# power_dist.net
KiCad netlist of a schematic drawn in EAGLE
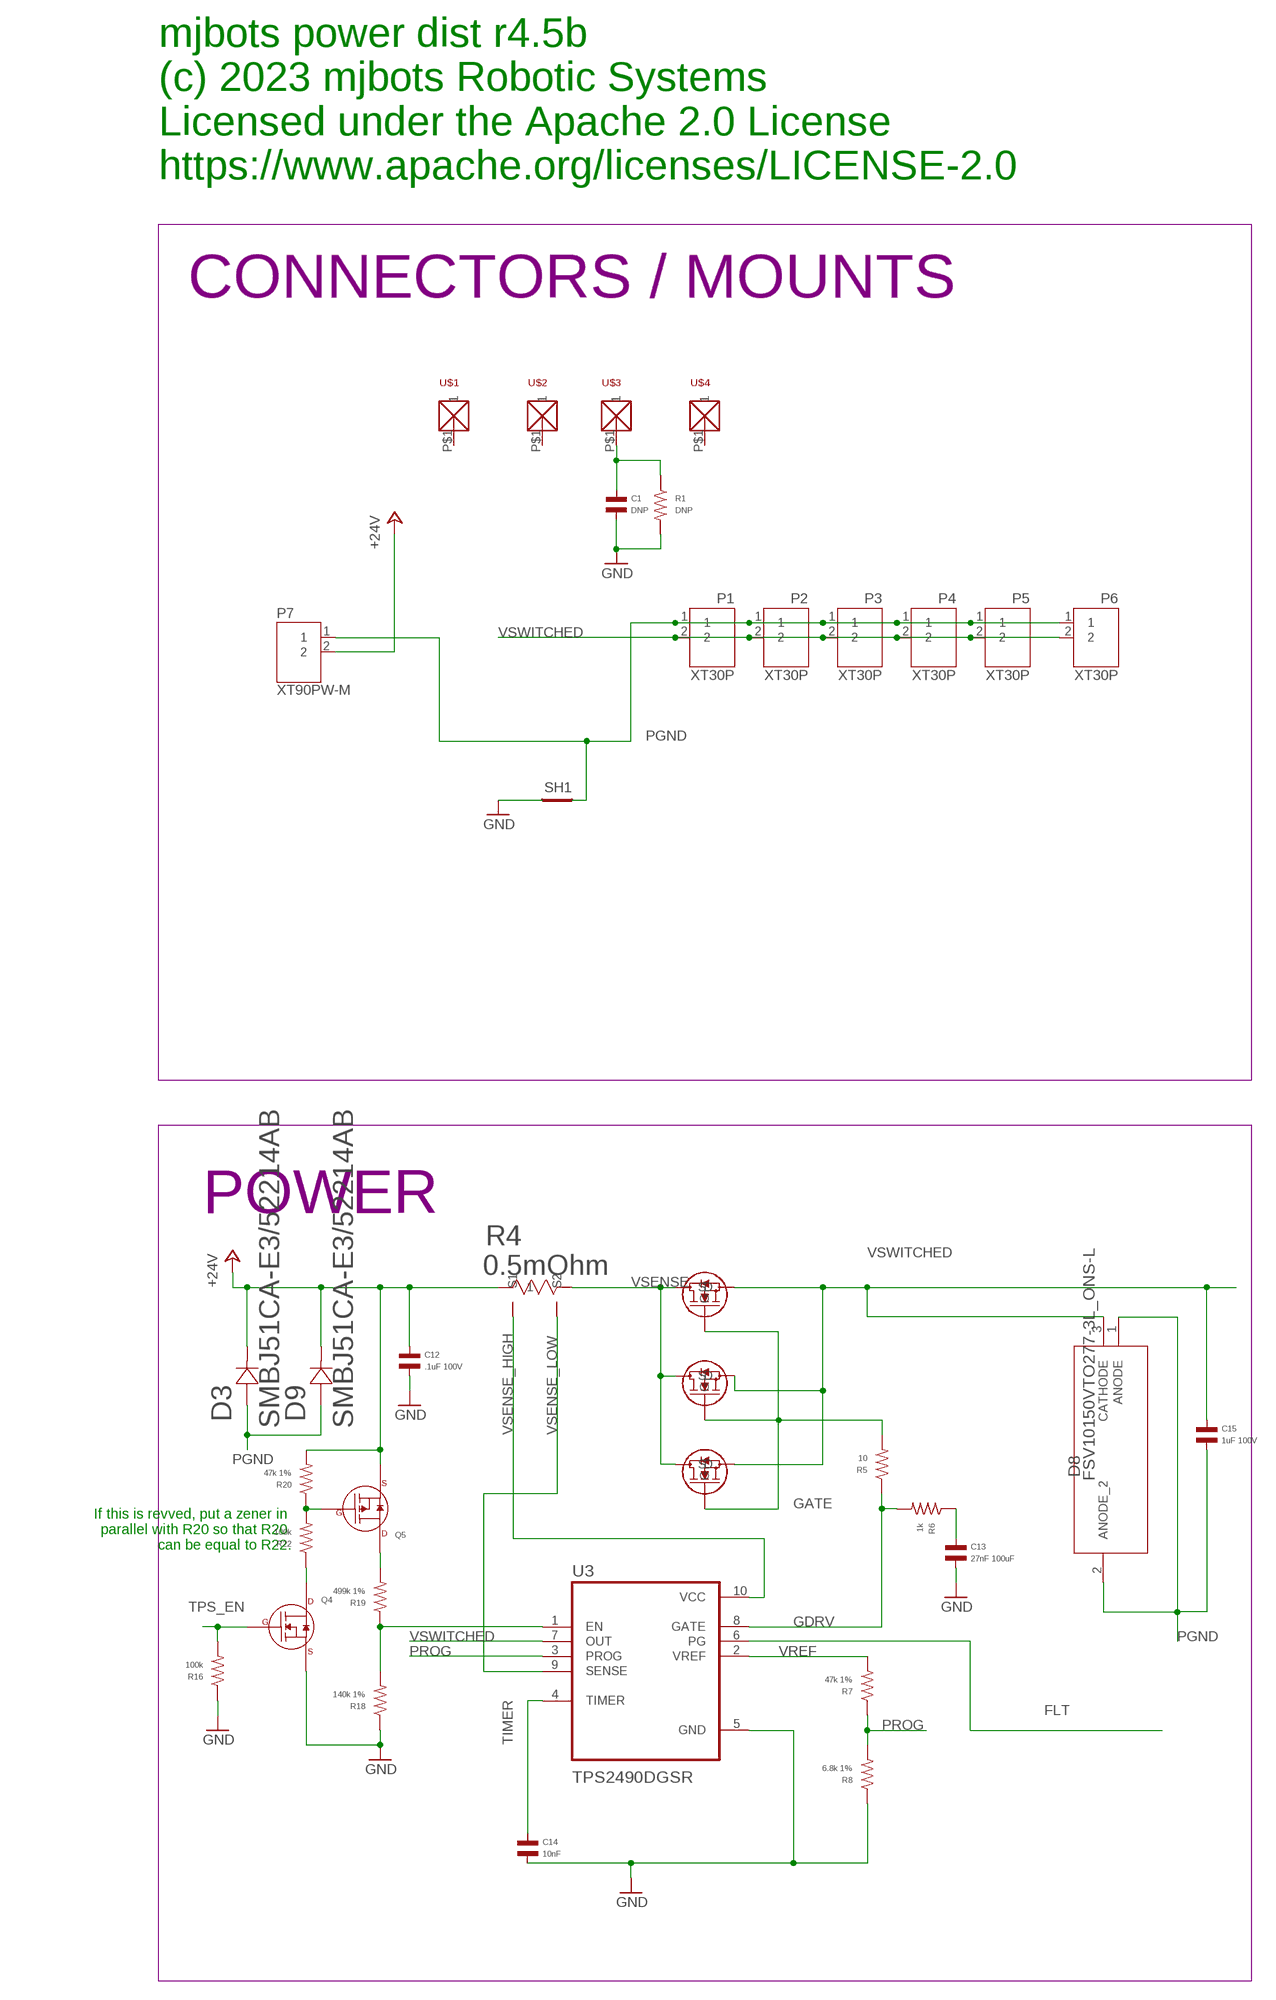
[diagram p0: schematic, sheet 1, part 1 of 2]
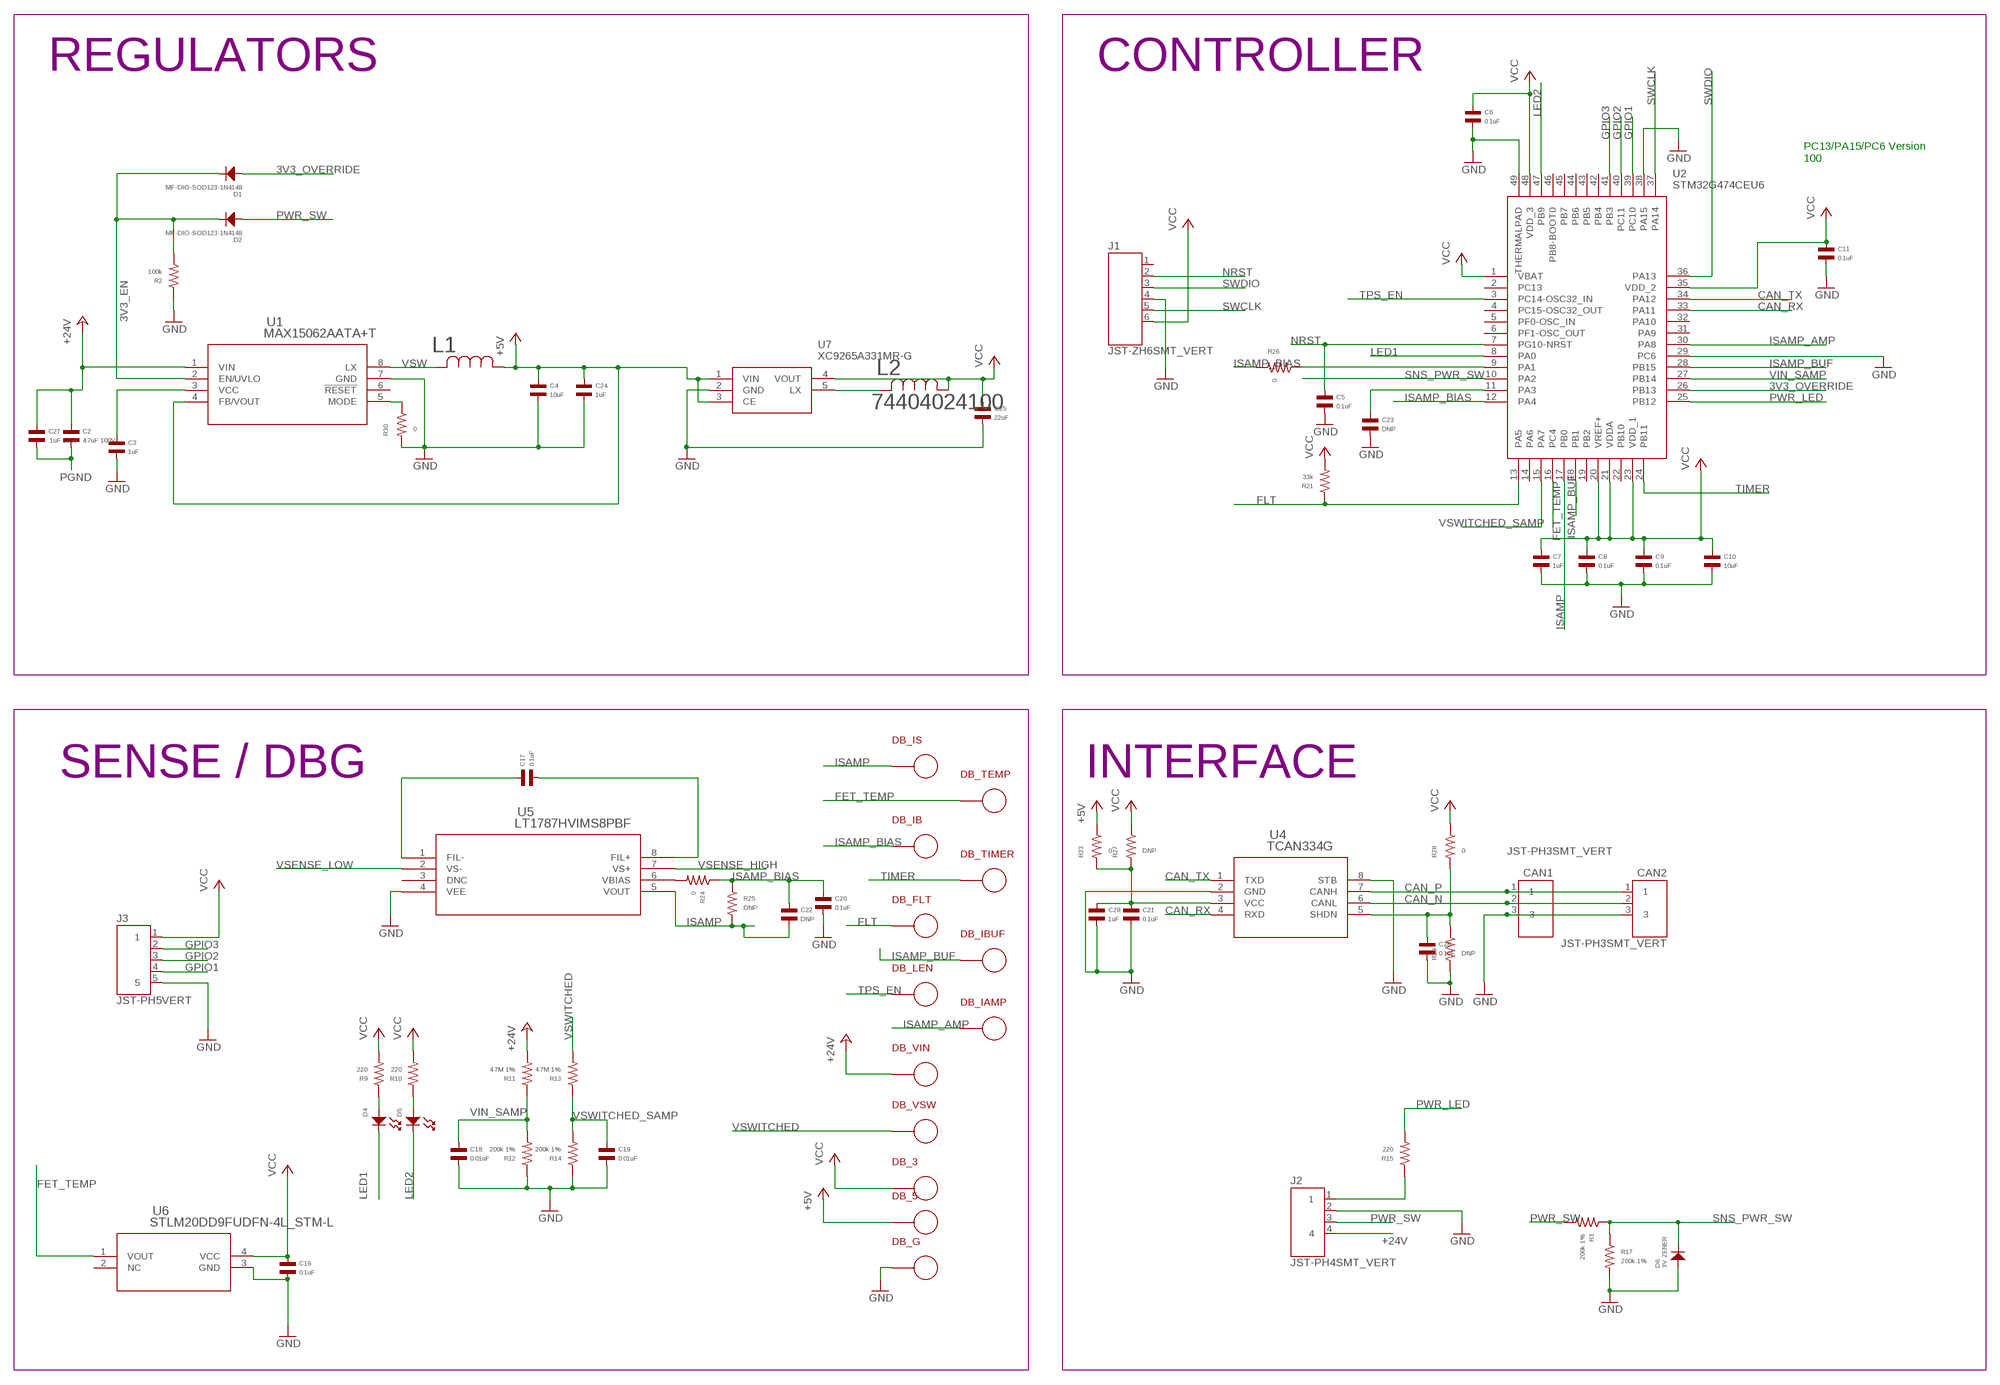
[diagram p1: schematic, sheet 1, part 2 of 2]

(export (version "E")
  (design (tool "Eeschema 10.0.6"))
  (components
    (comp (ref "C1")
      (value "DNP")
      (footprint "eagle-import:C0603")
      (fields (field (name "POPULATE") "0"))
      (libsource (lib "eagle-import") (part "CAPACITOR_NP_0603"))
    )
    (comp (ref "C2")
      (value "4.7uF 100V")
      (footprint "eagle-import:C1206")
      (fields (field (name "MF") "MURATA") (field (name "MPN") "GRJ31CC72A475KE01K"))
      (libsource (lib "eagle-import") (part "CAPACITOR_NP_1206"))
    )
    (comp (ref "C3")
      (value "1uF")
      (footprint "eagle-import:C0603")
      (fields (field (name "HOUSEPART") "1") (field (name "MPN") "MF-CAP-0603-1uF"))
      (libsource (lib "eagle-import") (part "CAPACITOR_NP_0603"))
    )
    (comp (ref "C4")
      (value "10uF")
      (footprint "eagle-import:C1206")
      (fields (field (name "HOUSEPART") "1") (field (name "MPN") "MF-CAP-1206-10uF"))
      (libsource (lib "eagle-import") (part "CAPACITOR_NP_1206"))
    )
    (comp (ref "C5")
      (value "0.1uF")
      (footprint "eagle-import:C0603")
      (fields (field (name "HOUSEPART") "1") (field (name "MPN") "MF-CAP-0603-0.1uF"))
      (libsource (lib "eagle-import") (part "CAPACITOR_NP_0603"))
    )
    (comp (ref "C6")
      (value "0.1uF")
      (footprint "eagle-import:C0603")
      (fields (field (name "HOUSEPART") "1") (field (name "MPN") "MF-CAP-0603-0.1uF"))
      (libsource (lib "eagle-import") (part "CAPACITOR_NP_0603"))
    )
    (comp (ref "C7")
      (value "1uF")
      (footprint "eagle-import:C0603")
      (fields (field (name "HOUSEPART") "1") (field (name "MPN") "MF-CAP-0603-1uF"))
      (libsource (lib "eagle-import") (part "CAPACITOR_NP_0603"))
    )
    (comp (ref "C8")
      (value "0.1uF")
      (footprint "eagle-import:C0603")
      (fields (field (name "HOUSEPART") "1") (field (name "MPN") "MF-CAP-0603-0.1uF"))
      (libsource (lib "eagle-import") (part "CAPACITOR_NP_0603"))
    )
    (comp (ref "C9")
      (value "0.1uF")
      (footprint "eagle-import:C0603")
      (fields (field (name "HOUSEPART") "1") (field (name "MPN") "MF-CAP-0603-0.1uF"))
      (libsource (lib "eagle-import") (part "CAPACITOR_NP_0603"))
    )
    (comp (ref "C10")
      (value "10uF")
      (footprint "eagle-import:C1206")
      (fields (field (name "HOUSEPART") "1") (field (name "MPN") "MF-CAP-1206-10uF"))
      (libsource (lib "eagle-import") (part "CAPACITOR_NP_1206"))
    )
    (comp (ref "C11")
      (value "0.1uF")
      (footprint "eagle-import:C0603")
      (fields (field (name "HOUSEPART") "1") (field (name "MPN") "MF-CAP-0603-0.1uF"))
      (libsource (lib "eagle-import") (part "CAPACITOR_NP_0603"))
    )
    (comp (ref "C12")
      (value ".1uF 100V")
      (footprint "eagle-import:C0603")
      (fields (field (name "HOUSEPART") "0") (field (name "MPN") "GRM188R72A104KA35D"))
      (libsource (lib "eagle-import") (part "CAPACITOR_NP_0603"))
    )
    (comp (ref "C13")
      (value "27nF 100uF")
      (footprint "eagle-import:C0603")
      (fields (field (name "HOUSEPART") "0") (field (name "MPN") "C0603C273K1RAC7867"))
      (libsource (lib "eagle-import") (part "CAPACITOR_NP_0603"))
    )
    (comp (ref "C14")
      (value "10nF")
      (footprint "eagle-import:C0603")
      (fields (field (name "HOUSEPART") "1") (field (name "MPN") "MF-CAP-0603-0.01uF"))
      (libsource (lib "eagle-import") (part "CAPACITOR_NP_0603"))
    )
    (comp (ref "C15")
      (value "1uF 100V")
      (footprint "eagle-import:C0805")
      (fields (field (name "MF") "MURATA") (field (name "MPN") "GCM21BC72A105KE36L"))
      (libsource (lib "eagle-import") (part "CAPACITOR_NP_0805"))
    )
    (comp (ref "C16")
      (value "0.1uF")
      (footprint "eagle-import:C0603")
      (fields (field (name "HOUSEPART") "1") (field (name "MPN") "MF-CAP-0603-0.1uF"))
      (libsource (lib "eagle-import") (part "CAPACITOR_NP_0603"))
    )
    (comp (ref "C17")
      (value "0.1uF")
      (footprint "eagle-import:C0603")
      (fields (field (name "HOUSEPART") "1") (field (name "MPN") "MF-CAP-0603-0.1uF"))
      (libsource (lib "eagle-import") (part "CAPACITOR_NP_0603"))
    )
    (comp (ref "C18")
      (value "0.01uF")
      (footprint "eagle-import:C0603")
      (fields (field (name "HOUSEPART") "1") (field (name "MPN") "MF-CAP-0603-0.01uF"))
      (libsource (lib "eagle-import") (part "CAPACITOR_NP_0603"))
    )
    (comp (ref "C19")
      (value "0.01uF")
      (footprint "eagle-import:C0603")
      (fields (field (name "HOUSEPART") "1") (field (name "MPN") "MF-CAP-0603-0.01uF"))
      (libsource (lib "eagle-import") (part "CAPACITOR_NP_0603"))
    )
    (comp (ref "C20")
      (value "0.1uF")
      (footprint "eagle-import:C0603")
      (fields (field (name "HOUSEPART") "1") (field (name "MPN") "MF-CAP-0603-0.1uF"))
      (libsource (lib "eagle-import") (part "CAPACITOR_NP_0603"))
    )
    (comp (ref "C21")
      (value "0.1uF")
      (footprint "eagle-import:C0603")
      (fields (field (name "HOUSEPART") "1") (field (name "MPN") "MF-CAP-0603-0.1uF"))
      (libsource (lib "eagle-import") (part "CAPACITOR_NP_0603"))
    )
    (comp (ref "C22")
      (value "DNP")
      (footprint "eagle-import:C0603")
      (fields (field (name "HOUSEPART") "1") (field (name "POPULATE") "0"))
      (libsource (lib "eagle-import") (part "CAPACITOR_NP_0603"))
    )
    (comp (ref "C23")
      (value "DNP")
      (footprint "eagle-import:C0603")
      (fields (field (name "HOUSEPART") "1") (field (name "POPULATE") "0"))
      (libsource (lib "eagle-import") (part "CAPACITOR_NP_0603"))
    )
    (comp (ref "C24")
      (value "1uF")
      (footprint "eagle-import:C0402")
      (fields (field (name "HOUSEPART") "1") (field (name "MPN") "MF-CAP-0402-1uF"))
      (libsource (lib "eagle-import") (part "CAPACITOR_NP_0402"))
    )
    (comp (ref "C25")
      (value "22uF")
      (footprint "eagle-import:C1206")
      (fields (field (name "MF") "Samsung") (field (name "MPN") "CL31B226KPHNNNE"))
      (libsource (lib "eagle-import") (part "CAPACITOR_NP_1206"))
    )
    (comp (ref "C26")
      (value "0.1uF")
      (footprint "eagle-import:C0603")
      (fields (field (name "HOUSEPART") "1") (field (name "MPN") "MF-CAP-0603-0.1uF"))
      (libsource (lib "eagle-import") (part "CAPACITOR_NP_0603"))
    )
    (comp (ref "C27")
      (value ".1uF 100V")
      (footprint "eagle-import:C0603")
      (fields (field (name "HOUSEPART") "0") (field (name "MPN") "GRM188R72A104KA35D"))
      (libsource (lib "eagle-import") (part "CAPACITOR_NP_0603"))
    )
    (comp (ref "C28")
      (value "1uF")
      (footprint "eagle-import:C0603")
      (fields (field (name "HOUSEPART") "1") (field (name "MPN") "MF-CAP-0603-1uF"))
      (libsource (lib "eagle-import") (part "CAPACITOR_NP_0603"))
    )
    (comp (ref "CAN1")
      (value "JST-PH3SMT_VERT")
      (footprint "eagle-import:JST_B3B_PH-SM4-TB(LF)(SN)")
      (fields (field (name "MF") "JST") (field (name "MPN") "B3B-PH-SM4-TB(LF)(SN)"))
      (libsource (lib "eagle-import") (part "JST-PH3SMT_VERT"))
    )
    (comp (ref "CAN2")
      (value "JST-PH3SMT_VERT")
      (footprint "eagle-import:JST_B3B_PH-SM4-TB(LF)(SN)")
      (fields (field (name "MF") "JST") (field (name "MPN") "B3B-PH-SM4-TB(LF)(SN)"))
      (libsource (lib "eagle-import") (part "JST-PH3SMT_VERT"))
    )
    (comp (ref "D1")
      (value "MF-DIO-SOD123-1N4148")
      (footprint "eagle-import:SOD-123")
      (fields (field (name "HOUSEPART") "YES"))
      (libsource (lib "eagle-import") (part "DIODES_SOD-123_1N4148"))
    )
    (comp (ref "D2")
      (value "MF-DIO-SOD123-1N4148")
      (footprint "eagle-import:SOD-123")
      (fields (field (name "HOUSEPART") "YES"))
      (libsource (lib "eagle-import") (part "DIODES_SOD-123_1N4148"))
    )
    (comp (ref "D3")
      (value "SMBJ51CA-E3/52214AB")
      (footprint "eagle-import:DIODE_DO-214AB")
      (fields (field (name "MPN") "SMC5K51A-M3/I"))
      (libsource (lib "eagle-import") (part "SMBJ51CA-E3/52214AB"))
    )
    (comp (ref "D4")
      (value "LED_SINGLE-0603")
      (footprint "eagle-import:LED0603")
      (fields
        (field (name "HOUSEPART") "NO")
        (field (name "HOUSEPART_1") "1")
        (field (name "MPN") "MF-LED-0603-RED")
      )
      (libsource (lib "eagle-import") (part "LED_SINGLE-0603"))
    )
    (comp (ref "D5")
      (value "LED_SINGLE-0603")
      (footprint "eagle-import:LED0603")
      (fields
        (field (name "HOUSEPART") "NO")
        (field (name "HOUSEPART_1") "1")
        (field (name "MPN") "MF-LED-0603-RED")
      )
      (libsource (lib "eagle-import") (part "LED_SINGLE-0603"))
    )
    (comp (ref "D6")
      (value "3V ZENER")
      (footprint "eagle-import:SOD-123")
      (fields
        (field (name "HOUSEPART") "YES")
        (field (name "MPN") "MF-DIO-SOD123-1N4148")
        (field (name "MPN_1") "MMSZ4682T1G")
      )
      (libsource (lib "eagle-import") (part "DIODES_SOD-123_1N4148"))
    )
    (comp (ref "D8")
      (value "FSV10150VTO277-3L_ONS-L")
      (footprint "eagle-import:TO277-3L_ONS-L")
      (fields
        (field (name "MANUFACTURER_PART_NUMBER") "FSV10150V")
        (field (name "COPYRIGHT") "Copyright (C) 2018 Accelerated Designs. All rights reserved")
      )
      (libsource (lib "eagle-import") (part "FSV10150VTO277-3L_ONS-L"))
    )
    (comp (ref "D9")
      (value "SMBJ51CA-E3/52214AB")
      (footprint "eagle-import:DIODE_DO-214AB")
      (fields (field (name "MPN") "SMC5K51A-M3/I"))
      (libsource (lib "eagle-import") (part "SMBJ51CA-E3/52214AB"))
    )
    (comp (ref "DB_3")
      (value "PAD24AWG_PAD")
      (footprint "eagle-import:24AWG_PAD")
      (libsource (lib "eagle-import") (part "PAD24AWG_PAD"))
    )
    (comp (ref "DB_5")
      (value "PAD24AWG_PAD")
      (footprint "eagle-import:24AWG_PAD")
      (libsource (lib "eagle-import") (part "PAD24AWG_PAD"))
    )
    (comp (ref "DB_FLT")
      (value "PAD24AWG_PAD")
      (footprint "eagle-import:24AWG_PAD")
      (libsource (lib "eagle-import") (part "PAD24AWG_PAD"))
    )
    (comp (ref "DB_G")
      (value "PAD24AWG_PAD")
      (footprint "eagle-import:24AWG_PAD")
      (libsource (lib "eagle-import") (part "PAD24AWG_PAD"))
    )
    (comp (ref "DB_IAMP")
      (value "PAD24AWG_PAD")
      (footprint "eagle-import:24AWG_PAD")
      (libsource (lib "eagle-import") (part "PAD24AWG_PAD"))
    )
    (comp (ref "DB_IB")
      (value "PAD24AWG_PAD")
      (footprint "eagle-import:24AWG_PAD")
      (libsource (lib "eagle-import") (part "PAD24AWG_PAD"))
    )
    (comp (ref "DB_IBUF")
      (value "PAD24AWG_PAD")
      (footprint "eagle-import:24AWG_PAD")
      (libsource (lib "eagle-import") (part "PAD24AWG_PAD"))
    )
    (comp (ref "DB_IS")
      (value "PAD24AWG_PAD")
      (footprint "eagle-import:24AWG_PAD")
      (libsource (lib "eagle-import") (part "PAD24AWG_PAD"))
    )
    (comp (ref "DB_LEN")
      (value "PAD24AWG_PAD")
      (footprint "eagle-import:24AWG_PAD")
      (libsource (lib "eagle-import") (part "PAD24AWG_PAD"))
    )
    (comp (ref "DB_TEMP")
      (value "PAD24AWG_PAD")
      (footprint "eagle-import:24AWG_PAD")
      (libsource (lib "eagle-import") (part "PAD24AWG_PAD"))
    )
    (comp (ref "DB_TIMER")
      (value "PAD24AWG_PAD")
      (footprint "eagle-import:24AWG_PAD")
      (libsource (lib "eagle-import") (part "PAD24AWG_PAD"))
    )
    (comp (ref "DB_VIN")
      (value "PAD24AWG_PAD")
      (footprint "eagle-import:24AWG_PAD")
      (libsource (lib "eagle-import") (part "PAD24AWG_PAD"))
    )
    (comp (ref "DB_VSW")
      (value "PAD24AWG_PAD")
      (footprint "eagle-import:24AWG_PAD")
      (libsource (lib "eagle-import") (part "PAD24AWG_PAD"))
    )
    (comp (ref "J1")
      (value "JST-ZH6SMT_VERT")
      (footprint "eagle-import:JST_B6B-ZR-SM4-TF(LF)(SN)")
      (fields (field (name "MF") "JST") (field (name "MPN") "B6B-ZR-SM4-TF(LF)(SN)"))
      (libsource (lib "eagle-import") (part "JST-ZH6SMT_VERT"))
    )
    (comp (ref "J2")
      (value "JST-PH4SMT_VERT")
      (footprint "eagle-import:JST_B4B_PH-SM4-TB(LF)(SN)")
      (fields (field (name "MF") "JST") (field (name "MPN") "B4B-PH-SM4-TB(LF)(SN)"))
      (libsource (lib "eagle-import") (part "JST-PH4SMT_VERT"))
    )
    (comp (ref "J3")
      (value "JST-PH5VERT")
      (footprint "eagle-import:JST_B5B_PH-SM4-TB(LF)(SN)")
      (fields (field (name "MF") "JST") (field (name "MPN") "B5B-PH-SM4-TB(LF)(SN)"))
      (libsource (lib "eagle-import") (part "JST-PH5VERT"))
    )
    (comp (ref "L1")
      (value "SRN4018-220M")
      (footprint "eagle-import:IND_BOURNS_SRN4018")
      (fields
        (field (name "MANUFACTURER_PART_NUMBER") "SRN4018220M")
        (field (name "MANUFACTURER_PART_NUMBER_1") "74404042470")
        (field (name "MF") "Wurth Electronics")
        (field (name "MPN") "74404042470")
        (field (name "VENDOR") "Wurth")
      )
      (libsource (lib "eagle-import") (part "SRN4018-220M"))
    )
    (comp (ref "L2")
      (value "74404024100")
      (footprint "eagle-import:IND_4024100_WRE")
      (fields
        (field (name "MPN") "MF-RES-0805-0")
        (field (name "COPYRIGHT") "Copyright (C) 2022 Ultra Librarian. All rights reserved.")
      )
      (libsource (lib "eagle-import") (part "74404024100"))
    )
    (comp (ref "P1")
      (value "XT30P")
      (footprint "eagle-import:XT30P")
      (fields (field (name "MF") "AMASS") (field (name "MPN") "XT30UPB-F"))
      (libsource (lib "eagle-import") (part "XT30P"))
    )
    (comp (ref "P2")
      (value "XT30P")
      (footprint "eagle-import:XT30P")
      (fields (field (name "MF") "AMASS") (field (name "MPN") "XT30UPB-F"))
      (libsource (lib "eagle-import") (part "XT30P"))
    )
    (comp (ref "P3")
      (value "XT30P")
      (footprint "eagle-import:XT30P")
      (fields (field (name "MF") "AMASS") (field (name "MPN") "XT30UPB-F"))
      (libsource (lib "eagle-import") (part "XT30P"))
    )
    (comp (ref "P4")
      (value "XT30P")
      (footprint "eagle-import:XT30P")
      (fields (field (name "MF") "AMASS") (field (name "MPN") "XT30UPB-F"))
      (libsource (lib "eagle-import") (part "XT30P"))
    )
    (comp (ref "P5")
      (value "XT30P")
      (footprint "eagle-import:XT30P")
      (fields (field (name "MF") "AMASS") (field (name "MPN") "XT30UPB-F"))
      (libsource (lib "eagle-import") (part "XT30P"))
    )
    (comp (ref "P6")
      (value "XT30P")
      (footprint "eagle-import:XT30P")
      (fields (field (name "MF") "AMASS") (field (name "MPN") "XT30UPB-F"))
      (libsource (lib "eagle-import") (part "XT30P"))
    )
    (comp (ref "P7")
      (value "XT90PW-M")
      (footprint "eagle-import:XT90PW-M")
      (libsource (lib "eagle-import") (part "XT90PW-M"))
    )
    (comp (ref "Q1")
      (value "PSMN4R8-100BSEJ")
      (footprint "eagle-import:D2PAK_SOT404_NEX")
      (fields
        (field (name "MANUFACTURER_PART_NUMBER") "PSMN3R7-100BSE")
        (field (name "MPN") "PSMN3R7-100BSE")
        (field (name "COPYRIGHT") "Copyright (C) 2018 Accelerated Designs. All rights reserved")
      )
      (libsource (lib "eagle-import") (part "PSMN4R8-100BSEJ"))
    )
    (comp (ref "Q2")
      (value "PSMN4R8-100BSEJ")
      (footprint "eagle-import:D2PAK_SOT404_NEX")
      (fields
        (field (name "MANUFACTURER_PART_NUMBER") "PSMN3R7-100BSE")
        (field (name "MPN") "PSMN3R7-100BSE")
        (field (name "COPYRIGHT") "Copyright (C) 2018 Accelerated Designs. All rights reserved")
      )
      (libsource (lib "eagle-import") (part "PSMN4R8-100BSEJ"))
    )
    (comp (ref "Q3")
      (value "PSMN4R8-100BSEJ")
      (footprint "eagle-import:D2PAK_SOT404_NEX")
      (fields
        (field (name "MANUFACTURER_PART_NUMBER") "PSMN3R7-100BSE")
        (field (name "MPN") "PSMN3R7-100BSE")
        (field (name "COPYRIGHT") "Copyright (C) 2018 Accelerated Designs. All rights reserved")
      )
      (libsource (lib "eagle-import") (part "PSMN4R8-100BSEJ"))
    )
    (comp (ref "Q4")
      (value "N-CHANNEL_FET_SOT-23-3")
      (footprint "eagle-import:SOT-23-3")
      (fields (field (name "HOUSEPART") "NO") (field (name "MPN") "BSS123"))
      (libsource (lib "eagle-import") (part "N-CHANNEL_FET_SOT-23-3"))
    )
    (comp (ref "Q5")
      (value "P-CHANNEL_FET_SOT-23-3")
      (footprint "eagle-import:SOT-23-3")
      (fields (field (name "HOUSEPART") "NO") (field (name "MPN") "ZXMP10A13FTA"))
      (libsource (lib "eagle-import") (part "P-CHANNEL_FET_SOT-23-3"))
    )
    (comp (ref "R1")
      (value "DNP")
      (footprint "eagle-import:R0603")
      (fields (field (name "POPULATE") "0"))
      (libsource (lib "eagle-import") (part "RESISTOR_0603"))
    )
    (comp (ref "R2")
      (value "100k")
      (footprint "eagle-import:R0603")
      (fields (field (name "HOUSEPART") "1") (field (name "MPN") "MF-RES-0603-100K"))
      (libsource (lib "eagle-import") (part "RESISTOR_0603"))
    )
    (comp (ref "R3")
      (value "200k 1%")
      (footprint "eagle-import:R0603")
      (fields (field (name "HOUSEPART") "0") (field (name "MPN") "RC0603FR-07200KL"))
      (libsource (lib "eagle-import") (part "RESISTOR_0603"))
    )
    (comp (ref "R4")
      (value "0.5mOhm")
      (footprint "eagle-import:SHUNT2512")
      (fields (field (name "MF") "VISHAY DALE") (field (name "MPN") "WSLF2512L5000FEA"))
      (libsource (lib "eagle-import") (part "SENSE_RESISTOR2512"))
    )
    (comp (ref "R5")
      (value "10")
      (footprint "eagle-import:R0603")
      (fields (field (name "HOUSEPART") "1") (field (name "MPN") "MF-RES-0603-10"))
      (libsource (lib "eagle-import") (part "RESISTOR_0603"))
    )
    (comp (ref "R6")
      (value "1k")
      (footprint "eagle-import:R0603")
      (fields (field (name "HOUSEPART") "1") (field (name "MPN") "MF-RES-0603-1K"))
      (libsource (lib "eagle-import") (part "RESISTOR_0603"))
    )
    (comp (ref "R7")
      (value "47k 1%")
      (footprint "eagle-import:R0603")
      (fields (field (name "HOUSEPART") "0") (field (name "MPN") "RC0603FR-0747KL"))
      (libsource (lib "eagle-import") (part "RESISTOR_0603"))
    )
    (comp (ref "R8")
      (value "6.8k 1%")
      (footprint "eagle-import:R0603")
      (fields (field (name "HOUSEPART") "0") (field (name "MPN") "RC0603FR-076K8L"))
      (libsource (lib "eagle-import") (part "RESISTOR_0603"))
    )
    (comp (ref "R9")
      (value "220")
      (footprint "eagle-import:R0603")
      (fields (field (name "HOUSEPART") "1") (field (name "MPN") "MF-RES-0603-220"))
      (libsource (lib "eagle-import") (part "RESISTOR_0603"))
    )
    (comp (ref "R10")
      (value "220")
      (footprint "eagle-import:R0603")
      (fields (field (name "HOUSEPART") "1") (field (name "MPN") "MF-RES-0603-220"))
      (libsource (lib "eagle-import") (part "RESISTOR_0603"))
    )
    (comp (ref "R11")
      (value "4.7M 1%")
      (footprint "eagle-import:R0603")
      (fields (field (name "HOUSEPART") "0") (field (name "MPN") "RC0603FR-074M7L"))
      (libsource (lib "eagle-import") (part "RESISTOR_0603"))
    )
    (comp (ref "R12")
      (value "200k 1%")
      (footprint "eagle-import:R0603")
      (fields (field (name "HOUSEPART") "0") (field (name "MPN") "RC0603FR-07200KL"))
      (libsource (lib "eagle-import") (part "RESISTOR_0603"))
    )
    (comp (ref "R13")
      (value "4.7M 1%")
      (footprint "eagle-import:R0603")
      (fields (field (name "HOUSEPART") "0") (field (name "MPN") "RC0603FR-074M7L"))
      (libsource (lib "eagle-import") (part "RESISTOR_0603"))
    )
    (comp (ref "R14")
      (value "200k 1%")
      (footprint "eagle-import:R0603")
      (fields (field (name "HOUSEPART") "0") (field (name "MPN") "RC0603FR-07200KL"))
      (libsource (lib "eagle-import") (part "RESISTOR_0603"))
    )
    (comp (ref "R15")
      (value "220")
      (footprint "eagle-import:R0603")
      (fields (field (name "HOUSEPART") "1") (field (name "MPN") "MF-RES-0603-220"))
      (libsource (lib "eagle-import") (part "RESISTOR_0603"))
    )
    (comp (ref "R16")
      (value "100k")
      (footprint "eagle-import:R0603")
      (fields (field (name "HOUSEPART") "1") (field (name "MPN") "MF-RES-0603-100K"))
      (libsource (lib "eagle-import") (part "RESISTOR_0603"))
    )
    (comp (ref "R17")
      (value "200k 1%")
      (footprint "eagle-import:R0603")
      (fields (field (name "HOUSEPART") "0") (field (name "MPN") "RC0603FR-07200KL"))
      (libsource (lib "eagle-import") (part "RESISTOR_0603"))
    )
    (comp (ref "R18")
      (value "140k 1%")
      (footprint "eagle-import:R0603")
      (fields (field (name "HOUSEPART") "0") (field (name "MPN") "RC0603FR-07140KL"))
      (libsource (lib "eagle-import") (part "RESISTOR_0603"))
    )
    (comp (ref "R19")
      (value "499k 1%")
      (footprint "eagle-import:R0603")
      (fields (field (name "HOUSEPART") "0") (field (name "MPN") "RC0603FR-07499KL"))
      (libsource (lib "eagle-import") (part "RESISTOR_0603"))
    )
    (comp (ref "R20")
      (value "47k 1%")
      (footprint "eagle-import:R0603")
      (fields (field (name "HOUSEPART") "0") (field (name "MPN") "RC0603FR-0747KL"))
      (libsource (lib "eagle-import") (part "RESISTOR_0603"))
    )
    (comp (ref "R21")
      (value "33k")
      (footprint "eagle-import:R0603")
      (fields (field (name "HOUSEPART") "1") (field (name "MPN") "RC0603FR-0733KL"))
      (libsource (lib "eagle-import") (part "RESISTOR_0603"))
    )
    (comp (ref "R22")
      (value "100k")
      (footprint "eagle-import:R0603")
      (fields (field (name "HOUSEPART") "1") (field (name "MPN") "MF-RES-0603-100K"))
      (libsource (lib "eagle-import") (part "RESISTOR_0603"))
    )
    (comp (ref "R23")
      (value "0")
      (footprint "eagle-import:R0603")
      (fields (field (name "HOUSEPART") "1") (field (name "MPN") "MF-RES-0603-0"))
      (libsource (lib "eagle-import") (part "RESISTOR_0603"))
    )
    (comp (ref "R24")
      (value "0")
      (footprint "eagle-import:R0603")
      (fields (field (name "HOUSEPART") "1") (field (name "MPN") "MF-RES-0603-0"))
      (libsource (lib "eagle-import") (part "RESISTOR_0603"))
    )
    (comp (ref "R25")
      (value "DNP")
      (footprint "eagle-import:R0603")
      (fields (field (name "HOUSEPART") "1") (field (name "POPULATE") "0"))
      (libsource (lib "eagle-import") (part "RESISTOR_0603"))
    )
    (comp (ref "R26")
      (value "0")
      (footprint "eagle-import:R0603")
      (fields (field (name "HOUSEPART") "1") (field (name "MPN") "MF-RES-0603-0"))
      (libsource (lib "eagle-import") (part "RESISTOR_0603"))
    )
    (comp (ref "R27")
      (value "DNP")
      (footprint "eagle-import:R0603")
      (fields
        (field (name "HOUSEPART") "1")
        (field (name "MPN") "MF-RES-0603-0")
        (field (name "POPULATE") "0")
      )
      (libsource (lib "eagle-import") (part "RESISTOR_0603"))
    )
    (comp (ref "R28")
      (value "0")
      (footprint "eagle-import:R0603")
      (fields (field (name "HOUSEPART") "1") (field (name "MPN") "MF-RES-0603-0"))
      (libsource (lib "eagle-import") (part "RESISTOR_0603"))
    )
    (comp (ref "R29")
      (value "DNP")
      (footprint "eagle-import:R0603")
      (fields
        (field (name "HOUSEPART") "1")
        (field (name "MPN") "MF-RES-0603-0")
        (field (name "POPULATE") "0")
      )
      (libsource (lib "eagle-import") (part "RESISTOR_0603"))
    )
    (comp (ref "R30")
      (value "0")
      (footprint "eagle-import:R0603")
      (fields (field (name "HOUSEPART") "1") (field (name "MPN") "MF-RES-0603-0"))
      (libsource (lib "eagle-import") (part "RESISTOR_0603"))
    )
    (comp (ref "SH1")
      (value "SHORTMEDIUM")
      (footprint "eagle-import:SHORT_TOP-MEDIUM")
      (libsource (lib "eagle-import") (part "SHORTMEDIUM"))
    )
    (comp (ref "U$1")
      (value "MOUNT")
      (footprint "eagle-import:M2.5MOUNT")
      (libsource (lib "eagle-import") (part "MOUNT"))
    )
    (comp (ref "U$2")
      (value "MOUNT")
      (footprint "eagle-import:M2.5MOUNT")
      (libsource (lib "eagle-import") (part "MOUNT"))
    )
    (comp (ref "U$3")
      (value "MOUNT")
      (footprint "eagle-import:M2.5MOUNT")
      (libsource (lib "eagle-import") (part "MOUNT"))
    )
    (comp (ref "U$4")
      (value "MOUNT")
      (footprint "eagle-import:M2.5MOUNT")
      (libsource (lib "eagle-import") (part "MOUNT"))
    )
    (comp (ref "U1")
      (value "MAX15062AATA+T")
      (footprint "eagle-import:21-0487A_MXM")
      (fields
        (field (name "MANUFACTURER_PART_NUMBER") "MAX15062BATA+T")
        (field (name "MF") "Maxim")
        (field (name "MPN") "MAX15062BATA+T")
        (field (name "COPYRIGHT") "Copyright (C) 2018 Accelerated Designs. All rights reserved")
      )
      (libsource (lib "eagle-import") (part "MAX15062AATA+T"))
    )
    (comp (ref "U2")
      (value "STM32G474CEU6")
      (footprint "eagle-import:QFN50P700X700X60-49N")
      (fields (field (name "MOUSER_PART_NUMBER") "511-STM32G474CEU6") (field (name "MF") "ST"))
      (libsource (lib "eagle-import") (part "STM32G474CEU6"))
    )
    (comp (ref "U3")
      (value "TPS2490DGSR")
      (footprint "eagle-import:SOP50P490X110-10N")
      (fields (field (name "DIGI-KEY_PART_NUMBER") "296-26924-1-ND") (field (name "MF") "Texas Instruments"))
      (libsource (lib "eagle-import") (part "TPS2490DGSR"))
    )
    (comp (ref "U4")
      (value "TCAN334G")
      (footprint "eagle-import:SOIC8")
      (fields (field (name "MF") "TI") (field (name "MPN") "TCAN1057AEVDRQ1"))
      (libsource (lib "eagle-import") (part "TCAN334G"))
    )
    (comp (ref "U5")
      (value "LT1787HVIMS8PBF")
      (footprint "eagle-import:MSOP-8_MS")
      (fields
        (field (name "DIGI-KEY_PART_NUMBER") "LT1787HVIMS8#PBF-ND")
        (field (name "MF") "Linear Technology")
        (field (name "MP") "LT1787HVIMS8#PBF")
      )
      (libsource (lib "eagle-import") (part "LT1787HVIMS8PBF"))
    )
    (comp (ref "U6")
      (value "STLM20DD9FUDFN-4L_STM-L")
      (footprint "eagle-import:UDFN-4L_STM-L")
      (fields
        (field (name "MANUFACTURER_PART_NUMBER") "STLM20DD9F")
        (field (name "COPYRIGHT") "Copyright (C) 2018 Accelerated Designs. All rights reserved")
      )
      (libsource (lib "eagle-import") (part "STLM20DD9FUDFN-4L_STM-L"))
    )
    (comp (ref "U7")
      (value "XC9265A331MR-G")
      (footprint "eagle-import:SOT95P280X130-5N")
      (fields
        (field (name "MOUSER_PART_NUMBER") "865-XC9265A331MR-G")
        (field (name "MPN") "MF-REG-SOT235-3.3V-300mA")
      )
      (libsource (lib "eagle-import") (part "XC9265A331MR-G"))
    )
  )
  (nets
    (net (code "1") (name "+5V") (class "Default")
      (node (ref "C24") (pin "P$1") (pinfunction "P$1_P$1") (pintype "passive"))
      (node (ref "C4") (pin "P$1") (pinfunction "P$1_P$1") (pintype "passive"))
      (node (ref "DB_5") (pin "P$1") (pinfunction "P$1_P$1") (pintype "bidirectional"))
      (node (ref "L1") (pin "1") (pinfunction "1_1") (pintype "passive"))
      (node (ref "R23") (pin "P$1") (pinfunction "P$1_P$1") (pintype "passive"))
      (node (ref "U1") (pin "4") (pinfunction "FB/VOUT_4") (pintype "bidirectional"))
      (node (ref "U7") (pin "1") (pinfunction "VIN_1") (pintype "bidirectional"))
      (node (ref "U7") (pin "3") (pinfunction "CE_3") (pintype "bidirectional"))
    )
    (net (code "2") (name "+24V") (class "Default")
      (node (ref "C12") (pin "P$1") (pinfunction "P$1_P$1") (pintype "passive"))
      (node (ref "C2") (pin "P$1") (pinfunction "P$1_P$1") (pintype "passive"))
      (node (ref "C27") (pin "P$1") (pinfunction "P$1_P$1") (pintype "passive"))
      (node (ref "D3") (pin "P$1") (pinfunction "1_P$1") (pintype "passive"))
      (node (ref "D9") (pin "P$1") (pinfunction "1_P$1") (pintype "passive"))
      (node (ref "DB_VIN") (pin "P$1") (pinfunction "P$1_P$1") (pintype "bidirectional"))
      (node (ref "J2") (pin "4") (pinfunction "4_4") (pintype "passive"))
      (node (ref "P7") (pin "2") (pinfunction "2_2") (pintype "passive"))
      (node (ref "Q5") (pin "P$2") (pinfunction "SOURCE_P$2") (pintype "bidirectional"))
      (node (ref "R11") (pin "P$2") (pinfunction "P$2_P$2") (pintype "passive"))
      (node (ref "R20") (pin "P$2") (pinfunction "P$2_P$2") (pintype "passive"))
      (node (ref "R4") (pin "1") (pinfunction "1_1") (pintype "passive"))
      (node (ref "U1") (pin "1") (pinfunction "VIN_1") (pintype "input"))
    )
    (net (code "3") (name "/3V3_EN") (class "Default")
      (node (ref "D1") (pin "CATHODE") (pinfunction "CATHODE_CATHODE") (pintype "bidirectional"))
      (node (ref "D2") (pin "CATHODE") (pinfunction "CATHODE_CATHODE") (pintype "bidirectional"))
      (node (ref "R2") (pin "P$2") (pinfunction "P$2_P$2") (pintype "passive"))
      (node (ref "U1") (pin "2") (pinfunction "EN/UVLO_2") (pintype "input"))
    )
    (net (code "4") (name "/3V3_OVERRIDE") (class "Default")
      (node (ref "D1") (pin "ANODE") (pinfunction "ANODE_ANODE") (pintype "bidirectional"))
      (node (ref "U2") (pin "26") (pinfunction "PB13_26") (pintype "bidirectional"))
    )
    (net (code "5") (name "/CAN_N") (class "Default")
      (node (ref "CAN1") (pin "2") (pinfunction "2_2") (pintype "passive"))
      (node (ref "CAN2") (pin "2") (pinfunction "2_2") (pintype "passive"))
      (node (ref "U4") (pin "6") (pinfunction "CANL_6") (pintype "bidirectional"))
    )
    (net (code "6") (name "/CAN_P") (class "Default")
      (node (ref "CAN1") (pin "1") (pinfunction "1_1") (pintype "passive"))
      (node (ref "CAN2") (pin "1") (pinfunction "1_1") (pintype "passive"))
      (node (ref "U4") (pin "7") (pinfunction "CANH_7") (pintype "bidirectional"))
    )
    (net (code "7") (name "/CAN_RX") (class "Default")
      (node (ref "U2") (pin "33") (pinfunction "PA11_33") (pintype "bidirectional"))
      (node (ref "U4") (pin "4") (pinfunction "RXD_4") (pintype "output"))
    )
    (net (code "8") (name "/CAN_TX") (class "Default")
      (node (ref "U2") (pin "34") (pinfunction "PA12_34") (pintype "bidirectional"))
      (node (ref "U4") (pin "1") (pinfunction "TXD_1") (pintype "input"))
    )
    (net (code "9") (name "/FET_TEMP") (class "Default")
      (node (ref "DB_TEMP") (pin "P$1") (pinfunction "P$1_P$1") (pintype "bidirectional"))
      (node (ref "U2") (pin "16") (pinfunction "PC4_16") (pintype "bidirectional"))
      (node (ref "U6") (pin "1") (pinfunction "VOUT_1") (pintype "output"))
    )
    (net (code "10") (name "/FLT") (class "Default")
      (node (ref "DB_FLT") (pin "P$1") (pinfunction "P$1_P$1") (pintype "bidirectional"))
      (node (ref "R21") (pin "P$1") (pinfunction "P$1_P$1") (pintype "passive"))
      (node (ref "U2") (pin "13") (pinfunction "PA5_13") (pintype "bidirectional"))
      (node (ref "U3") (pin "6") (pinfunction "PG_6") (pintype "output"))
    )
    (net (code "11") (name "/GATE") (class "Default")
      (node (ref "Q1") (pin "1") (pinfunction "G_1") (pintype "passive"))
      (node (ref "Q2") (pin "1") (pinfunction "G_1") (pintype "passive"))
      (node (ref "Q3") (pin "1") (pinfunction "G_1") (pintype "passive"))
      (node (ref "R5") (pin "P$2") (pinfunction "P$2_P$2") (pintype "passive"))
    )
    (net (code "12") (name "/GDRV") (class "Default")
      (node (ref "R5") (pin "P$1") (pinfunction "P$1_P$1") (pintype "passive"))
      (node (ref "R6") (pin "P$2") (pinfunction "P$2_P$2") (pintype "passive"))
      (node (ref "U3") (pin "8") (pinfunction "GATE_8") (pintype "output"))
    )
    (net (code "13") (name "/GPIO1") (class "Default")
      (node (ref "J3") (pin "4") (pinfunction "4_4") (pintype "passive"))
      (node (ref "U2") (pin "39") (pinfunction "PC10_39") (pintype "bidirectional"))
    )
    (net (code "14") (name "/GPIO2") (class "Default")
      (node (ref "J3") (pin "3") (pinfunction "3_3") (pintype "passive"))
      (node (ref "U2") (pin "40") (pinfunction "PC11_40") (pintype "bidirectional"))
    )
    (net (code "15") (name "/GPIO3") (class "Default")
      (node (ref "J3") (pin "2") (pinfunction "2_2") (pintype "passive"))
      (node (ref "U2") (pin "41") (pinfunction "PB3_41") (pintype "bidirectional"))
    )
    (net (code "16") (name "/ISAMP") (class "Default")
      (node (ref "C22") (pin "P$2") (pinfunction "P$2_P$2") (pintype "passive"))
      (node (ref "DB_IS") (pin "P$1") (pinfunction "P$1_P$1") (pintype "bidirectional"))
      (node (ref "R25") (pin "P$2") (pinfunction "P$2_P$2") (pintype "passive"))
      (node (ref "U2") (pin "17") (pinfunction "PB0_17") (pintype "bidirectional"))
      (node (ref "U5") (pin "5") (pinfunction "VOUT_5") (pintype "output"))
    )
    (net (code "17") (name "/ISAMP_AMP") (class "Default")
      (node (ref "DB_IAMP") (pin "P$1") (pinfunction "P$1_P$1") (pintype "bidirectional"))
      (node (ref "U2") (pin "30") (pinfunction "PA8_30") (pintype "bidirectional"))
    )
    (net (code "18") (name "/ISAMP_BIAS") (class "Default")
      (node (ref "C20") (pin "P$1") (pinfunction "P$1_P$1") (pintype "passive"))
      (node (ref "C22") (pin "P$1") (pinfunction "P$1_P$1") (pintype "passive"))
      (node (ref "DB_IB") (pin "P$1") (pinfunction "P$1_P$1") (pintype "bidirectional"))
      (node (ref "R24") (pin "P$1") (pinfunction "P$1_P$1") (pintype "passive"))
      (node (ref "R25") (pin "P$1") (pinfunction "P$1_P$1") (pintype "passive"))
      (node (ref "R26") (pin "P$2") (pinfunction "P$2_P$2") (pintype "passive"))
      (node (ref "U2") (pin "12") (pinfunction "PA4_12") (pintype "bidirectional"))
    )
    (net (code "19") (name "/ISAMP_BUF") (class "Default")
      (node (ref "DB_IBUF") (pin "P$1") (pinfunction "P$1_P$1") (pintype "bidirectional"))
      (node (ref "U2") (pin "18") (pinfunction "PB1_18") (pintype "bidirectional"))
      (node (ref "U2") (pin "28") (pinfunction "PB15_28") (pintype "bidirectional"))
    )
    (net (code "20") (name "/LED1") (class "Default")
      (node (ref "D4") (pin "CATHODE") (pinfunction "CATHODE_CATHODE") (pintype "power_in"))
      (node (ref "U2") (pin "8") (pinfunction "PA0_8") (pintype "bidirectional"))
    )
    (net (code "21") (name "/LED2") (class "Default")
      (node (ref "D5") (pin "CATHODE") (pinfunction "CATHODE_CATHODE") (pintype "power_in"))
      (node (ref "U2") (pin "47") (pinfunction "PB9_47") (pintype "bidirectional"))
    )
    (net (code "22") (name "/NRST") (class "Default")
      (node (ref "C5") (pin "P$1") (pinfunction "P$1_P$1") (pintype "passive"))
      (node (ref "J1") (pin "2") (pinfunction "2_2") (pintype "passive"))
      (node (ref "U2") (pin "7") (pinfunction "PG10-NRST_7") (pintype "bidirectional"))
    )
    (net (code "23") (name "/PGND") (class "Default")
      (node (ref "C15") (pin "P$2") (pinfunction "P$2_P$2") (pintype "passive"))
      (node (ref "C2") (pin "P$2") (pinfunction "P$2_P$2") (pintype "passive"))
      (node (ref "C27") (pin "P$2") (pinfunction "P$2_P$2") (pintype "passive"))
      (node (ref "D3") (pin "P$2") (pinfunction "2_P$2") (pintype "passive"))
      (node (ref "D8") (pin "1") (pinfunction "ANODE_1") (pintype "passive"))
      (node (ref "D8") (pin "2") (pinfunction "ANODE_2_2") (pintype "passive"))
      (node (ref "D9") (pin "P$2") (pinfunction "2_P$2") (pintype "passive"))
      (node (ref "P1") (pin "1") (pinfunction "1_1") (pintype "passive"))
      (node (ref "P2") (pin "1") (pinfunction "1_1") (pintype "passive"))
      (node (ref "P3") (pin "1") (pinfunction "1_1") (pintype "passive"))
      (node (ref "P4") (pin "1") (pinfunction "1_1") (pintype "passive"))
      (node (ref "P5") (pin "1") (pinfunction "1_1") (pintype "passive"))
      (node (ref "P6") (pin "1") (pinfunction "1_1") (pintype "passive"))
      (node (ref "P7") (pin "1") (pinfunction "1_1") (pintype "passive"))
      (node (ref "SH1") (pin "2") (pinfunction "P$2_2") (pintype "bidirectional"))
    )
    (net (code "24") (name "/PROG") (class "Default")
      (node (ref "R7") (pin "P$1") (pinfunction "P$1_P$1") (pintype "passive"))
      (node (ref "R8") (pin "P$2") (pinfunction "P$2_P$2") (pintype "passive"))
      (node (ref "U3") (pin "3") (pinfunction "PROG_3") (pintype "input"))
    )
    (net (code "25") (name "/PWR_LED") (class "Default")
      (node (ref "R15") (pin "P$2") (pinfunction "P$2_P$2") (pintype "passive"))
      (node (ref "U2") (pin "25") (pinfunction "PB12_25") (pintype "bidirectional"))
    )
    (net (code "26") (name "/PWR_SW") (class "Default")
      (node (ref "D2") (pin "ANODE") (pinfunction "ANODE_ANODE") (pintype "bidirectional"))
      (node (ref "J2") (pin "3") (pinfunction "3_3") (pintype "passive"))
      (node (ref "R3") (pin "P$2") (pinfunction "P$2_P$2") (pintype "passive"))
    )
    (net (code "27") (name "/SNS_PWR_SW") (class "Default")
      (node (ref "D6") (pin "CATHODE") (pinfunction "CATHODE_CATHODE") (pintype "bidirectional"))
      (node (ref "R17") (pin "P$1") (pinfunction "P$1_P$1") (pintype "passive"))
      (node (ref "R3") (pin "P$1") (pinfunction "P$1_P$1") (pintype "passive"))
      (node (ref "U2") (pin "10") (pinfunction "PA2_10") (pintype "bidirectional"))
    )
    (net (code "28") (name "/SWCLK") (class "Default")
      (node (ref "J1") (pin "5") (pinfunction "5_5") (pintype "passive"))
      (node (ref "U2") (pin "37") (pinfunction "PA14_37") (pintype "bidirectional"))
    )
    (net (code "29") (name "/SWDIO") (class "Default")
      (node (ref "J1") (pin "3") (pinfunction "3_3") (pintype "passive"))
      (node (ref "U2") (pin "36") (pinfunction "PA13_36") (pintype "bidirectional"))
    )
    (net (code "30") (name "/TIMER") (class "Default")
      (node (ref "C14") (pin "P$1") (pinfunction "P$1_P$1") (pintype "passive"))
      (node (ref "DB_TIMER") (pin "P$1") (pinfunction "P$1_P$1") (pintype "bidirectional"))
      (node (ref "U2") (pin "24") (pinfunction "PB11_24") (pintype "bidirectional"))
      (node (ref "U3") (pin "4") (pinfunction "TIMER_4") (pintype "bidirectional"))
    )
    (net (code "31") (name "/TPS_EN") (class "Default")
      (node (ref "DB_LEN") (pin "P$1") (pinfunction "P$1_P$1") (pintype "bidirectional"))
      (node (ref "Q4") (pin "P$1") (pinfunction "GATE_P$1") (pintype "bidirectional"))
      (node (ref "R16") (pin "P$2") (pinfunction "P$2_P$2") (pintype "passive"))
      (node (ref "U2") (pin "3") (pinfunction "PC14-OSC32_IN_3") (pintype "bidirectional"))
    )
    (net (code "32") (name "/VIN_SAMP") (class "Default")
      (node (ref "C18") (pin "P$1") (pinfunction "P$1_P$1") (pintype "passive"))
      (node (ref "R11") (pin "P$1") (pinfunction "P$1_P$1") (pintype "passive"))
      (node (ref "R12") (pin "P$2") (pinfunction "P$2_P$2") (pintype "passive"))
      (node (ref "U2") (pin "27") (pinfunction "PB14_27") (pintype "bidirectional"))
    )
    (net (code "33") (name "/VREF") (class "Default")
      (node (ref "R7") (pin "P$2") (pinfunction "P$2_P$2") (pintype "passive"))
      (node (ref "U3") (pin "2") (pinfunction "VREF_2") (pintype "output"))
    )
    (net (code "34") (name "/VSENSE") (class "Default")
      (node (ref "Q1") (pin "2") (pinfunction "D_2") (pintype "passive"))
      (node (ref "Q2") (pin "2") (pinfunction "D_2") (pintype "passive"))
      (node (ref "Q3") (pin "2") (pinfunction "D_2") (pintype "passive"))
      (node (ref "R4") (pin "2") (pinfunction "2_2") (pintype "passive"))
    )
    (net (code "35") (name "/VSENSE_HIGH") (class "Default")
      (node (ref "R4") (pin "3") (pinfunction "S1_3") (pintype "passive"))
      (node (ref "U3") (pin "10") (pinfunction "VCC_10") (pintype "power_in"))
      (node (ref "U5") (pin "7") (pinfunction "VS+_7") (pintype "input"))
    )
    (net (code "36") (name "/VSENSE_LOW") (class "Default")
      (node (ref "R4") (pin "4") (pinfunction "S2_4") (pintype "passive"))
      (node (ref "U3") (pin "9") (pinfunction "SENSE_9") (pintype "input"))
      (node (ref "U5") (pin "2") (pinfunction "VS-_2") (pintype "input"))
    )
    (net (code "37") (name "/VSW") (class "Default")
      (node (ref "L1") (pin "2") (pinfunction "2_2") (pintype "passive"))
      (node (ref "U1") (pin "8") (pinfunction "LX_8") (pintype "passive"))
    )
    (net (code "38") (name "/VSWITCHED") (class "Default")
      (node (ref "C15") (pin "P$1") (pinfunction "P$1_P$1") (pintype "passive"))
      (node (ref "D8") (pin "3") (pinfunction "CATHODE_3") (pintype "passive"))
      (node (ref "DB_VSW") (pin "P$1") (pinfunction "P$1_P$1") (pintype "bidirectional"))
      (node (ref "P1") (pin "2") (pinfunction "2_2") (pintype "passive"))
      (node (ref "P2") (pin "2") (pinfunction "2_2") (pintype "passive"))
      (node (ref "P3") (pin "2") (pinfunction "2_2") (pintype "passive"))
      (node (ref "P4") (pin "2") (pinfunction "2_2") (pintype "passive"))
      (node (ref "P5") (pin "2") (pinfunction "2_2") (pintype "passive"))
      (node (ref "P6") (pin "2") (pinfunction "2_2") (pintype "passive"))
      (node (ref "Q1") (pin "3") (pinfunction "S_3") (pintype "passive"))
      (node (ref "Q2") (pin "3") (pinfunction "S_3") (pintype "passive"))
      (node (ref "Q3") (pin "3") (pinfunction "S_3") (pintype "passive"))
      (node (ref "R13") (pin "P$2") (pinfunction "P$2_P$2") (pintype "passive"))
      (node (ref "U3") (pin "7") (pinfunction "OUT_7") (pintype "input"))
    )
    (net (code "39") (name "/VSWITCHED_SAMP") (class "Default")
      (node (ref "C19") (pin "P$1") (pinfunction "P$1_P$1") (pintype "passive"))
      (node (ref "R13") (pin "P$1") (pinfunction "P$1_P$1") (pintype "passive"))
      (node (ref "R14") (pin "P$2") (pinfunction "P$2_P$2") (pintype "passive"))
      (node (ref "U2") (pin "15") (pinfunction "PA7_15") (pintype "bidirectional"))
    )
    (net (code "40") (name "GND") (class "Default")
      (node (ref "C1") (pin "P$2") (pinfunction "P$2_P$2") (pintype "passive"))
      (node (ref "C10") (pin "P$2") (pinfunction "P$2_P$2") (pintype "passive"))
      (node (ref "C11") (pin "P$2") (pinfunction "P$2_P$2") (pintype "passive"))
      (node (ref "C12") (pin "P$2") (pinfunction "P$2_P$2") (pintype "passive"))
      (node (ref "C13") (pin "P$2") (pinfunction "P$2_P$2") (pintype "passive"))
      (node (ref "C14") (pin "P$2") (pinfunction "P$2_P$2") (pintype "passive"))
      (node (ref "C16") (pin "P$2") (pinfunction "P$2_P$2") (pintype "passive"))
      (node (ref "C18") (pin "P$2") (pinfunction "P$2_P$2") (pintype "passive"))
      (node (ref "C19") (pin "P$2") (pinfunction "P$2_P$2") (pintype "passive"))
      (node (ref "C20") (pin "P$2") (pinfunction "P$2_P$2") (pintype "passive"))
      (node (ref "C21") (pin "P$2") (pinfunction "P$2_P$2") (pintype "passive"))
      (node (ref "C23") (pin "P$2") (pinfunction "P$2_P$2") (pintype "passive"))
      (node (ref "C24") (pin "P$2") (pinfunction "P$2_P$2") (pintype "passive"))
      (node (ref "C25") (pin "P$2") (pinfunction "P$2_P$2") (pintype "passive"))
      (node (ref "C26") (pin "P$2") (pinfunction "P$2_P$2") (pintype "passive"))
      (node (ref "C28") (pin "P$2") (pinfunction "P$2_P$2") (pintype "passive"))
      (node (ref "C3") (pin "P$2") (pinfunction "P$2_P$2") (pintype "passive"))
      (node (ref "C4") (pin "P$2") (pinfunction "P$2_P$2") (pintype "passive"))
      (node (ref "C5") (pin "P$2") (pinfunction "P$2_P$2") (pintype "passive"))
      (node (ref "C6") (pin "P$2") (pinfunction "P$2_P$2") (pintype "passive"))
      (node (ref "C7") (pin "P$2") (pinfunction "P$2_P$2") (pintype "passive"))
      (node (ref "C8") (pin "P$2") (pinfunction "P$2_P$2") (pintype "passive"))
      (node (ref "C9") (pin "P$2") (pinfunction "P$2_P$2") (pintype "passive"))
      (node (ref "CAN1") (pin "3") (pinfunction "3_3") (pintype "passive"))
      (node (ref "CAN2") (pin "3") (pinfunction "3_3") (pintype "passive"))
      (node (ref "D6") (pin "ANODE") (pinfunction "ANODE_ANODE") (pintype "bidirectional"))
      (node (ref "DB_G") (pin "P$1") (pinfunction "P$1_P$1") (pintype "bidirectional"))
      (node (ref "J1") (pin "4") (pinfunction "4_4") (pintype "passive"))
      (node (ref "J2") (pin "2") (pinfunction "2_2") (pintype "passive"))
      (node (ref "J3") (pin "5") (pinfunction "5_5") (pintype "passive"))
      (node (ref "Q4") (pin "P$2") (pinfunction "SOURCE_P$2") (pintype "bidirectional"))
      (node (ref "R1") (pin "P$2") (pinfunction "P$2_P$2") (pintype "passive"))
      (node (ref "R12") (pin "P$1") (pinfunction "P$1_P$1") (pintype "passive"))
      (node (ref "R14") (pin "P$1") (pinfunction "P$1_P$1") (pintype "passive"))
      (node (ref "R16") (pin "P$1") (pinfunction "P$1_P$1") (pintype "passive"))
      (node (ref "R17") (pin "P$2") (pinfunction "P$2_P$2") (pintype "passive"))
      (node (ref "R18") (pin "P$1") (pinfunction "P$1_P$1") (pintype "passive"))
      (node (ref "R2") (pin "P$1") (pinfunction "P$1_P$1") (pintype "passive"))
      (node (ref "R29") (pin "P$2") (pinfunction "P$2_P$2") (pintype "passive"))
      (node (ref "R30") (pin "P$2") (pinfunction "P$2_P$2") (pintype "passive"))
      (node (ref "R8") (pin "P$1") (pinfunction "P$1_P$1") (pintype "passive"))
      (node (ref "SH1") (pin "1") (pinfunction "P$1_1") (pintype "bidirectional"))
      (node (ref "U1") (pin "7") (pinfunction "GND_7") (pintype "power_in"))
      (node (ref "U2") (pin "29") (pinfunction "PC6_29") (pintype "bidirectional"))
      (node (ref "U2") (pin "38") (pinfunction "PA15_38") (pintype "bidirectional"))
      (node (ref "U2") (pin "49") (pinfunction "THERMALPAD_49") (pintype "bidirectional"))
      (node (ref "U3") (pin "5") (pinfunction "GND_5") (pintype "power_in"))
      (node (ref "U4") (pin "2") (pinfunction "GND_2") (pintype "power_in"))
      (node (ref "U4") (pin "8") (pinfunction "STB_8") (pintype "input"))
      (node (ref "U5") (pin "4") (pinfunction "VEE_4") (pintype "power_in"))
      (node (ref "U6") (pin "3") (pinfunction "GND_3") (pintype "power_in"))
      (node (ref "U7") (pin "2") (pinfunction "GND_2") (pintype "bidirectional"))
    )
    (net (code "41") (name "Net-(C13-PadP$1)") (class "Default")
      (node (ref "C13") (pin "P$1") (pinfunction "P$1_P$1") (pintype "passive"))
      (node (ref "R6") (pin "P$1") (pinfunction "P$1_P$1") (pintype "passive"))
    )
    (net (code "42") (name "Net-(D4-PadANODE)") (class "Default")
      (node (ref "D4") (pin "ANODE") (pinfunction "ANODE_ANODE") (pintype "power_in"))
      (node (ref "R9") (pin "P$1") (pinfunction "P$1_P$1") (pintype "passive"))
    )
    (net (code "43") (name "Net-(D5-PadANODE)") (class "Default")
      (node (ref "D5") (pin "ANODE") (pinfunction "ANODE_ANODE") (pintype "power_in"))
      (node (ref "R10") (pin "P$1") (pinfunction "P$1_P$1") (pintype "passive"))
    )
    (net (code "44") (name "Net-(J2-Pad1)") (class "Default")
      (node (ref "J2") (pin "1") (pinfunction "1_1") (pintype "passive"))
      (node (ref "R15") (pin "P$1") (pinfunction "P$1_P$1") (pintype "passive"))
    )
    (net (code "45") (name "Net-(Q4-DRAIN)") (class "Default")
      (node (ref "Q4") (pin "P$3") (pinfunction "DRAIN_P$3") (pintype "bidirectional"))
      (node (ref "R22") (pin "P$1") (pinfunction "P$1_P$1") (pintype "passive"))
    )
    (net (code "46") (name "Net-(Q5-DRAIN)") (class "Default")
      (node (ref "Q5") (pin "P$3") (pinfunction "DRAIN_P$3") (pintype "bidirectional"))
      (node (ref "R19") (pin "P$2") (pinfunction "P$2_P$2") (pintype "passive"))
    )
    (net (code "47") (name "Net-(Q5-GATE)") (class "Default")
      (node (ref "Q5") (pin "P$1") (pinfunction "GATE_P$1") (pintype "bidirectional"))
      (node (ref "R20") (pin "P$1") (pinfunction "P$1_P$1") (pintype "passive"))
      (node (ref "R22") (pin "P$2") (pinfunction "P$2_P$2") (pintype "passive"))
    )
    (net (code "48") (name "Net-(U$3-1)") (class "Default")
      (node (ref "C1") (pin "P$1") (pinfunction "P$1_P$1") (pintype "passive"))
      (node (ref "R1") (pin "P$1") (pinfunction "P$1_P$1") (pintype "passive"))
      (node (ref "U$3") (pin "P$1") (pinfunction "1_P$1") (pintype "passive"))
    )
    (net (code "49") (name "Net-(U1-MODE)") (class "Default")
      (node (ref "R30") (pin "P$1") (pinfunction "P$1_P$1") (pintype "passive"))
      (node (ref "U1") (pin "5") (pinfunction "MODE_5") (pintype "input"))
    )
    (net (code "50") (name "Net-(U1-VCC)") (class "Default")
      (node (ref "C3") (pin "P$1") (pinfunction "P$1_P$1") (pintype "passive"))
      (node (ref "U1") (pin "3") (pinfunction "VCC_3") (pintype "power_in"))
    )
    (net (code "51") (name "Net-(U2-PA1)") (class "Default")
      (node (ref "R26") (pin "P$1") (pinfunction "P$1_P$1") (pintype "passive"))
      (node (ref "U2") (pin "9") (pinfunction "PA1_9") (pintype "bidirectional"))
    )
    (net (code "52") (name "Net-(U2-PA3)") (class "Default")
      (node (ref "C23") (pin "P$1") (pinfunction "P$1_P$1") (pintype "passive"))
      (node (ref "U2") (pin "11") (pinfunction "PA3_11") (pintype "bidirectional"))
    )
    (net (code "53") (name "Net-(U3-EN)") (class "Default")
      (node (ref "R18") (pin "P$2") (pinfunction "P$2_P$2") (pintype "passive"))
      (node (ref "R19") (pin "P$1") (pinfunction "P$1_P$1") (pintype "passive"))
      (node (ref "U3") (pin "1") (pinfunction "EN_1") (pintype "input"))
    )
    (net (code "54") (name "Net-(U4-SHDN)") (class "Default")
      (node (ref "C26") (pin "P$1") (pinfunction "P$1_P$1") (pintype "passive"))
      (node (ref "R28") (pin "P$2") (pinfunction "P$2_P$2") (pintype "passive"))
      (node (ref "R29") (pin "P$1") (pinfunction "P$1_P$1") (pintype "passive"))
      (node (ref "U4") (pin "5") (pinfunction "SHDN_5") (pintype "input"))
    )
    (net (code "55") (name "Net-(U4-VCC)") (class "Default")
      (node (ref "C21") (pin "P$1") (pinfunction "P$1_P$1") (pintype "passive"))
      (node (ref "C28") (pin "P$1") (pinfunction "P$1_P$1") (pintype "passive"))
      (node (ref "R23") (pin "P$2") (pinfunction "P$2_P$2") (pintype "passive"))
      (node (ref "R27") (pin "P$2") (pinfunction "P$2_P$2") (pintype "passive"))
      (node (ref "U4") (pin "3") (pinfunction "VCC_3") (pintype "power_in"))
    )
    (net (code "56") (name "Net-(U5-FIL+)") (class "Default")
      (node (ref "C17") (pin "P$2") (pinfunction "P$2_P$2") (pintype "passive"))
      (node (ref "U5") (pin "8") (pinfunction "FIL+_8") (pintype "passive"))
    )
    (net (code "57") (name "Net-(U5-FIL-)") (class "Default")
      (node (ref "C17") (pin "P$1") (pinfunction "P$1_P$1") (pintype "passive"))
      (node (ref "U5") (pin "1") (pinfunction "FIL-_1") (pintype "passive"))
    )
    (net (code "58") (name "Net-(U5-VBIAS)") (class "Default")
      (node (ref "R24") (pin "P$2") (pinfunction "P$2_P$2") (pintype "passive"))
      (node (ref "U5") (pin "6") (pinfunction "VBIAS_6") (pintype "output"))
    )
    (net (code "59") (name "Net-(U7-LX)") (class "Default")
      (node (ref "L2") (pin "2") (pinfunction "2_2") (pintype "passive"))
      (node (ref "U7") (pin "5") (pinfunction "LX_5") (pintype "bidirectional"))
    )
    (net (code "60") (name "VCC") (class "Default")
      (node (ref "C10") (pin "P$1") (pinfunction "P$1_P$1") (pintype "passive"))
      (node (ref "C11") (pin "P$1") (pinfunction "P$1_P$1") (pintype "passive"))
      (node (ref "C16") (pin "P$1") (pinfunction "P$1_P$1") (pintype "passive"))
      (node (ref "C25") (pin "P$1") (pinfunction "P$1_P$1") (pintype "passive"))
      (node (ref "C6") (pin "P$1") (pinfunction "P$1_P$1") (pintype "passive"))
      (node (ref "C7") (pin "P$1") (pinfunction "P$1_P$1") (pintype "passive"))
      (node (ref "C8") (pin "P$1") (pinfunction "P$1_P$1") (pintype "passive"))
      (node (ref "C9") (pin "P$1") (pinfunction "P$1_P$1") (pintype "passive"))
      (node (ref "DB_3") (pin "P$1") (pinfunction "P$1_P$1") (pintype "bidirectional"))
      (node (ref "J1") (pin "6") (pinfunction "6_6") (pintype "passive"))
      (node (ref "J3") (pin "1") (pinfunction "1_1") (pintype "passive"))
      (node (ref "L2") (pin "1") (pinfunction "1_1") (pintype "passive"))
      (node (ref "R10") (pin "P$2") (pinfunction "P$2_P$2") (pintype "passive"))
      (node (ref "R21") (pin "P$2") (pinfunction "P$2_P$2") (pintype "passive"))
      (node (ref "R27") (pin "P$1") (pinfunction "P$1_P$1") (pintype "passive"))
      (node (ref "R28") (pin "P$1") (pinfunction "P$1_P$1") (pintype "passive"))
      (node (ref "R9") (pin "P$2") (pinfunction "P$2_P$2") (pintype "passive"))
      (node (ref "U2") (pin "1") (pinfunction "VBAT_1") (pintype "bidirectional"))
      (node (ref "U2") (pin "20") (pinfunction "VREF+_20") (pintype "bidirectional"))
      (node (ref "U2") (pin "21") (pinfunction "VDDA_21") (pintype "bidirectional"))
      (node (ref "U2") (pin "23") (pinfunction "VDD_1_23") (pintype "bidirectional"))
      (node (ref "U2") (pin "35") (pinfunction "VDD_2_35") (pintype "bidirectional"))
      (node (ref "U2") (pin "48") (pinfunction "VDD_3_48") (pintype "bidirectional"))
      (node (ref "U6") (pin "4") (pinfunction "VCC_4") (pintype "power_in"))
      (node (ref "U7") (pin "4") (pinfunction "VOUT_4") (pintype "bidirectional"))
    )
    (net (code "61") (name "unconnected-(J1-Pad1)") (class "Default")
      (node (ref "J1") (pin "1") (pinfunction "1_1") (pintype "passive"))
    )
    (net (code "62") (name "unconnected-(U$1-1-PadP$1)") (class "Default")
      (node (ref "U$1") (pin "P$1") (pinfunction "1_P$1") (pintype "passive"))
    )
    (net (code "63") (name "unconnected-(U$2-1-PadP$1)") (class "Default")
      (node (ref "U$2") (pin "P$1") (pinfunction "1_P$1") (pintype "passive"))
    )
    (net (code "64") (name "unconnected-(U$4-1-PadP$1)") (class "Default")
      (node (ref "U$4") (pin "P$1") (pinfunction "1_P$1") (pintype "passive"))
    )
    (net (code "65") (name "unconnected-(U1-~{RESET}-Pad6)") (class "Default")
      (node (ref "U1") (pin "6") (pinfunction "~{RESET}_6") (pintype "output"))
    )
    (net (code "66") (name "unconnected-(U2-PA6-Pad14)") (class "Default")
      (node (ref "U2") (pin "14") (pinfunction "PA6_14") (pintype "bidirectional"))
    )
    (net (code "67") (name "unconnected-(U2-PA9-Pad31)") (class "Default")
      (node (ref "U2") (pin "31") (pinfunction "PA9_31") (pintype "bidirectional"))
    )
    (net (code "68") (name "unconnected-(U2-PA10-Pad32)") (class "Default")
      (node (ref "U2") (pin "32") (pinfunction "PA10_32") (pintype "bidirectional"))
    )
    (net (code "69") (name "unconnected-(U2-PB2-Pad19)") (class "Default")
      (node (ref "U2") (pin "19") (pinfunction "PB2_19") (pintype "bidirectional"))
    )
    (net (code "70") (name "unconnected-(U2-PB4-Pad42)") (class "Default")
      (node (ref "U2") (pin "42") (pinfunction "PB4_42") (pintype "bidirectional"))
    )
    (net (code "71") (name "unconnected-(U2-PB5-Pad43)") (class "Default")
      (node (ref "U2") (pin "43") (pinfunction "PB5_43") (pintype "bidirectional"))
    )
    (net (code "72") (name "unconnected-(U2-PB6-Pad44)") (class "Default")
      (node (ref "U2") (pin "44") (pinfunction "PB6_44") (pintype "bidirectional"))
    )
    (net (code "73") (name "unconnected-(U2-PB7-Pad45)") (class "Default")
      (node (ref "U2") (pin "45") (pinfunction "PB7_45") (pintype "bidirectional"))
    )
    (net (code "74") (name "unconnected-(U2-PB8-BOOT0-Pad46)") (class "Default")
      (node (ref "U2") (pin "46") (pinfunction "PB8-BOOT0_46") (pintype "bidirectional"))
    )
    (net (code "75") (name "unconnected-(U2-PB10-Pad22)") (class "Default")
      (node (ref "U2") (pin "22") (pinfunction "PB10_22") (pintype "bidirectional"))
    )
    (net (code "76") (name "unconnected-(U2-PC13-Pad2)") (class "Default")
      (node (ref "U2") (pin "2") (pinfunction "PC13_2") (pintype "bidirectional"))
    )
    (net (code "77") (name "unconnected-(U2-PC15-OSC32_OUT-Pad4)") (class "Default")
      (node (ref "U2") (pin "4") (pinfunction "PC15-OSC32_OUT_4") (pintype "bidirectional"))
    )
    (net (code "78") (name "unconnected-(U2-PF0-OSC_IN-Pad5)") (class "Default")
      (node (ref "U2") (pin "5") (pinfunction "PF0-OSC_IN_5") (pintype "bidirectional"))
    )
    (net (code "79") (name "unconnected-(U2-PF1-OSC_OUT-Pad6)") (class "Default")
      (node (ref "U2") (pin "6") (pinfunction "PF1-OSC_OUT_6") (pintype "bidirectional"))
    )
    (net (code "80") (name "unconnected-(U5-DNC-Pad3)") (class "Default")
      (node (ref "U5") (pin "3") (pinfunction "DNC_3") (pintype "no_connect"))
    )
    (net (code "81") (name "unconnected-(U6-NC-Pad2)") (class "Default")
      (node (ref "U6") (pin "2") (pinfunction "NC_2") (pintype "no_connect"))
    )
  )
)
